# STC8G1K08.net
KiCad netlist of a schematic drawn in EasyEDA Pro
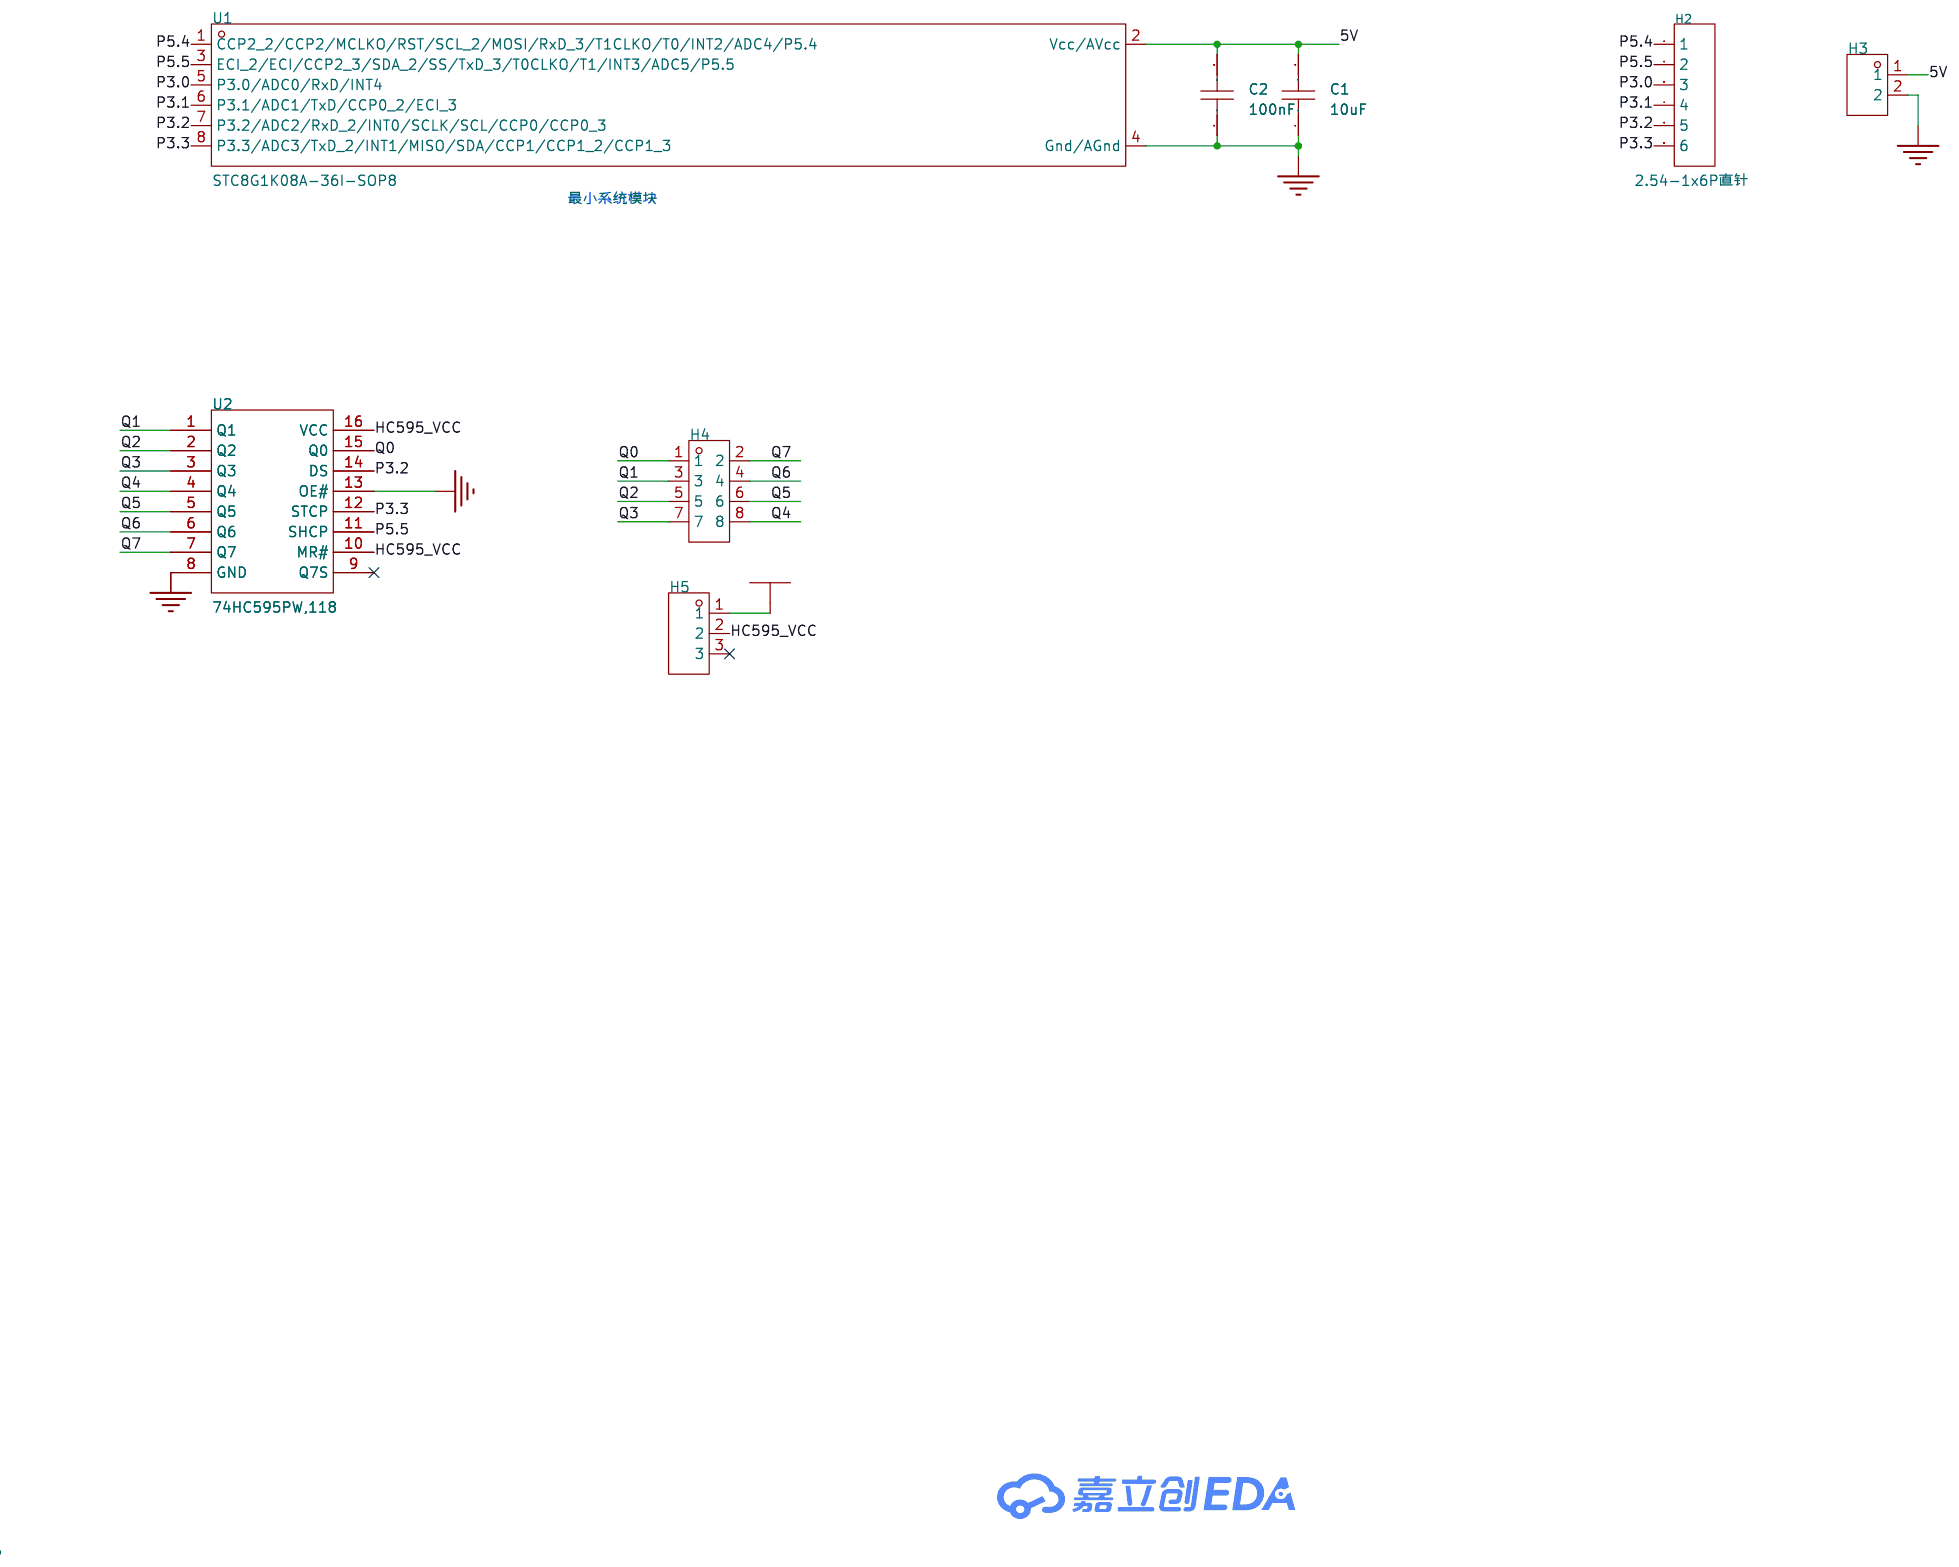
[diagram p0: schematic sheet]

(export (version "E")
  (design (tool "Eeschema 10.0.6"))
  (components
    (comp (ref "C1")
      (value "10uF")
      (footprint "easyedapro:C0603")
      (description "容值:10uF;精度:±10%;额定电压:10V;材质(温度系数):X5R;")
      (fields
        (field (name "Manufacturer Part") "CL10A106KP8NNNC")
        (field (name "Manufacturer") "SAMSUNG(三星)")
      )
      (libsource (lib "easyedapro") (part "CL10A106KP8NNNC"))
    )
    (comp (ref "C2")
      (value "100nF")
      (footprint "easyedapro:C0603")
      (description "容值:100nF;精度:±10%;额定电压:50V;材质(温度系数):X7R;")
      (fields
        (field (name "Manufacturer Part") "CC0603KRX7R9BB104")
        (field (name "Manufacturer") "YAGEO(国巨)")
      )
      (libsource (lib "easyedapro") (part "CC0603KRX7R9BB104"))
    )
    (comp (ref "H2")
      (value "2.54-1x6P直针")
      (footprint "easyedapro:HDR-TH_6P-P2.54-V-M-1")
      (fields (field (name "Manufacturer") "BOOMELE(博穆精密)"))
      (libsource (lib "easyedapro") (part "Header-Male-2.54_1x6"))
    )
    (comp (ref "H3")
      (value "PZ254V-11-02P")
      (footprint "easyedapro:HDR-TH_2P-P2.54-V-M")
      (fields (field (name "Manufacturer") "XFCN(兴飞)"))
      (libsource (lib "easyedapro") (part "PZ254V-11-02P"))
    )
    (comp (ref "H4")
      (value "PZ254V-12-8P")
      (footprint "easyedapro:HDR-TH_8P-P2.54-V-M-R2-C4-S2.54")
      (fields (field (name "Manufacturer") "XFCN(兴飞)"))
      (libsource (lib "easyedapro") (part "PZ254V-12-8P"))
    )
    (comp (ref "H5")
      (value "PZ254V-11-03P")
      (footprint "easyedapro:HDR-TH_3P-P2.54-V-M")
      (fields (field (name "Manufacturer") "XFCN(兴飞)"))
      (libsource (lib "easyedapro") (part "PZ254V-11-03P"))
    )
    (comp (ref "U1")
      (value "STC8G1K08A-36I-SOP8")
      (footprint "easyedapro:SOP-8_L5.0-W4.0-P1.27-LS6.0-BL")
      (description "CPU内核:51系列;应用领域:-;")
      (fields (field (name "Manufacturer") "STC"))
      (libsource (lib "easyedapro") (part "STC8G1K08A-36I-SOP8"))
    )
    (comp (ref "U2")
      (value "74HC595PW,118")
      (footprint "easyedapro:TSSOP-16_L5.0-W4.4-P0.65-LS6.4-BL")
      (fields (field (name "Manufacturer") "Nexperia(安世)"))
      (libsource (lib "easyedapro") (part "74HC595PW,118"))
    )
  )
  (nets
    (net (code "1") (name "/HC595_VCC") (class "Default")
      (node (ref "H5") (pin "2") (pinfunction "2_2") (pintype "input"))
      (node (ref "U2") (pin "10") (pinfunction "MR#_10") (pintype "input"))
      (node (ref "U2") (pin "16") (pinfunction "VCC_16") (pintype "input"))
    )
    (net (code "2") (name "/P3.0") (class "Default")
      (node (ref "H2") (pin "3") (pinfunction "3_3") (pintype "input"))
      (node (ref "U1") (pin "5") (pinfunction "P3.0/ADC0/RxD/INT4_5") (pintype "unspecified"))
    )
    (net (code "3") (name "/P3.1") (class "Default")
      (node (ref "H2") (pin "4") (pinfunction "4_4") (pintype "input"))
      (node (ref "U1") (pin "6") (pinfunction "P3.1/ADC1/TxD/CCP0_2/ECI_3_6") (pintype "unspecified"))
    )
    (net (code "4") (name "/P3.2") (class "Default")
      (node (ref "H2") (pin "5") (pinfunction "5_5") (pintype "input"))
      (node (ref "U1") (pin "7") (pinfunction "P3.2/ADC2/RxD_2/INT0/SCLK/SCL/CCP0/CCP0_3_7") (pintype "unspecified"))
      (node (ref "U2") (pin "14") (pinfunction "DS_14") (pintype "input"))
    )
    (net (code "5") (name "/P3.3") (class "Default")
      (node (ref "H2") (pin "6") (pinfunction "6_6") (pintype "input"))
      (node (ref "U1") (pin "8") (pinfunction "P3.3/ADC3/TxD_2/INT1/MISO/SDA/CCP1/CCP1_2/CCP1_3_8") (pintype "unspecified"))
      (node (ref "U2") (pin "12") (pinfunction "STCP_12") (pintype "input"))
    )
    (net (code "6") (name "/P5.4") (class "Default")
      (node (ref "H2") (pin "1") (pinfunction "1_1") (pintype "input"))
      (node (ref "U1") (pin "1") (pinfunction "CCP2_2/CCP2/MCLKO/RST/SCL_2/MOSI/RxD_3/T1CLKO/T0/INT2/ADC4/P5.4_1") (pintype "unspecified"))
    )
    (net (code "7") (name "/P5.5") (class "Default")
      (node (ref "H2") (pin "2") (pinfunction "2_2") (pintype "input"))
      (node (ref "U1") (pin "3") (pinfunction "ECI_2/ECI/CCP2_3/SDA_2/SS/TxD_3/T0CLKO/T1/INT3/ADC5/P5.5_3") (pintype "unspecified"))
      (node (ref "U2") (pin "11") (pinfunction "SHCP_11") (pintype "input"))
    )
    (net (code "8") (name "/Q0") (class "Default")
      (node (ref "H4") (pin "1") (pinfunction "1_1") (pintype "input"))
      (node (ref "U2") (pin "15") (pinfunction "Q0_15") (pintype "input"))
    )
    (net (code "9") (name "/Q1") (class "Default")
      (node (ref "H4") (pin "3") (pinfunction "3_3") (pintype "input"))
      (node (ref "U2") (pin "1") (pinfunction "Q1_1") (pintype "input"))
    )
    (net (code "10") (name "/Q2") (class "Default")
      (node (ref "H4") (pin "5") (pinfunction "5_5") (pintype "input"))
      (node (ref "U2") (pin "2") (pinfunction "Q2_2") (pintype "input"))
    )
    (net (code "11") (name "/Q3") (class "Default")
      (node (ref "H4") (pin "7") (pinfunction "7_7") (pintype "input"))
      (node (ref "U2") (pin "3") (pinfunction "Q3_3") (pintype "input"))
    )
    (net (code "12") (name "/Q4") (class "Default")
      (node (ref "H4") (pin "8") (pinfunction "8_8") (pintype "input"))
      (node (ref "U2") (pin "4") (pinfunction "Q4_4") (pintype "input"))
    )
    (net (code "13") (name "/Q5") (class "Default")
      (node (ref "H4") (pin "6") (pinfunction "6_6") (pintype "input"))
      (node (ref "U2") (pin "5") (pinfunction "Q5_5") (pintype "input"))
    )
    (net (code "14") (name "/Q6") (class "Default")
      (node (ref "H4") (pin "4") (pinfunction "4_4") (pintype "input"))
      (node (ref "U2") (pin "6") (pinfunction "Q6_6") (pintype "input"))
    )
    (net (code "15") (name "/Q7") (class "Default")
      (node (ref "H4") (pin "2") (pinfunction "2_2") (pintype "input"))
      (node (ref "U2") (pin "7") (pinfunction "Q7_7") (pintype "input"))
    )
    (net (code "16") (name "5V") (class "Default")
      (node (ref "C1") (pin "2") (pinfunction "2_2") (pintype "input"))
      (node (ref "C2") (pin "2") (pinfunction "2_2") (pintype "input"))
      (node (ref "H3") (pin "1") (pinfunction "1_1") (pintype "input"))
      (node (ref "H5") (pin "1") (pinfunction "1_1") (pintype "input"))
      (node (ref "U1") (pin "2") (pinfunction "Vcc/AVcc_2") (pintype "unspecified"))
    )
    (net (code "17") (name "GND") (class "Default")
      (node (ref "C1") (pin "1") (pinfunction "1_1") (pintype "input"))
      (node (ref "C2") (pin "1") (pinfunction "1_1") (pintype "input"))
      (node (ref "H3") (pin "2") (pinfunction "2_2") (pintype "input"))
      (node (ref "U1") (pin "4") (pinfunction "Gnd/AGnd_4") (pintype "unspecified"))
      (node (ref "U2") (pin "13") (pinfunction "OE#_13") (pintype "input"))
      (node (ref "U2") (pin "8") (pinfunction "GND_8") (pintype "input"))
    )
    (net (code "18") (name "unconnected-(H5-Pad3)") (class "Default")
      (node (ref "H5") (pin "3") (pinfunction "3_3") (pintype "input+no_connect"))
    )
    (net (code "19") (name "unconnected-(U2-Q7S-Pad9)") (class "Default")
      (node (ref "U2") (pin "9") (pinfunction "Q7S_9") (pintype "input+no_connect"))
    )
  )
)
